# Badge_03v2-prog-schem.net
KiCad netlist of a schematic drawn in EAGLE
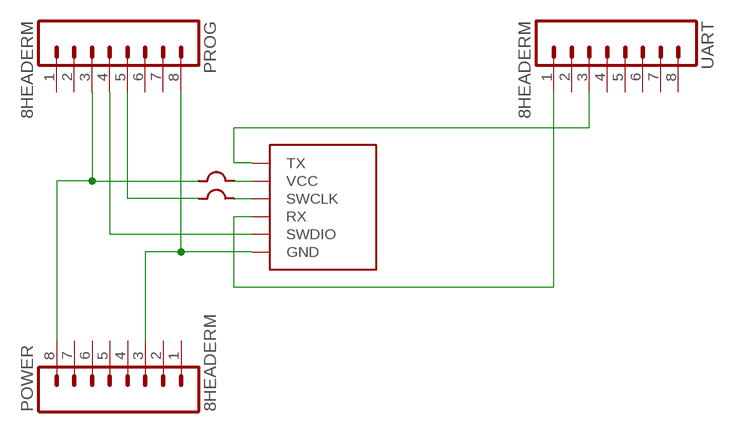
[diagram p0: schematic, sheet 1]

(export (version "E")
  (design (tool "Eeschema 10.0.6"))
  (components
    (comp (ref "J1")
      (value "PROG_CONN_6")
      (footprint "eagle-import:TH_CONN_6")
      (libsource (lib "eagle-import") (part "PROG_CONN_6"))
    )
    (comp (ref "POWER")
      (value "8HEADERM")
      (footprint "eagle-import:1X08_ROUND")
      (libsource (lib "eagle-import") (part "8HEADERM"))
    )
    (comp (ref "PROG")
      (value "8HEADERM")
      (footprint "eagle-import:1X08_ROUND")
      (libsource (lib "eagle-import") (part "8HEADERM"))
    )
    (comp (ref "U$1")
      (value "JUMPER")
      (footprint "eagle-import:1206")
      (libsource (lib "eagle-import") (part "JUMPER"))
    )
    (comp (ref "U$2")
      (value "JUMPER")
      (footprint "eagle-import:1206")
      (libsource (lib "eagle-import") (part "JUMPER"))
    )
    (comp (ref "UART")
      (value "8HEADERM")
      (footprint "eagle-import:1X08_ROUND")
      (libsource (lib "eagle-import") (part "8HEADERM"))
    )
  )
  (nets
    (net (code "1") (name "Net-(J1-PadGND)") (class "Default")
      (node (ref "J1") (pin "GND") (pinfunction "GND_GND") (pintype "bidirectional"))
      (node (ref "POWER") (pin "3") (pinfunction "3_3") (pintype "passive"))
      (node (ref "PROG") (pin "8") (pinfunction "8_8") (pintype "passive"))
    )
    (net (code "2") (name "Net-(J1-PadRX)") (class "Default")
      (node (ref "J1") (pin "RX") (pinfunction "RX_RX") (pintype "bidirectional"))
      (node (ref "UART") (pin "1") (pinfunction "1_1") (pintype "passive"))
    )
    (net (code "3") (name "Net-(J1-PadSWDIO)") (class "Default")
      (node (ref "J1") (pin "SWDIO") (pinfunction "SWDIO_SWDIO") (pintype "bidirectional"))
      (node (ref "PROG") (pin "4") (pinfunction "4_4") (pintype "passive"))
    )
    (net (code "4") (name "Net-(J1-PadTX)") (class "Default")
      (node (ref "J1") (pin "TX") (pinfunction "TX_TX") (pintype "bidirectional"))
      (node (ref "UART") (pin "3") (pinfunction "3_3") (pintype "passive"))
    )
    (net (code "5") (name "Net-(U$1-P$1)") (class "Default")
      (node (ref "POWER") (pin "8") (pinfunction "8_8") (pintype "passive"))
      (node (ref "PROG") (pin "3") (pinfunction "3_3") (pintype "passive"))
      (node (ref "U$1") (pin "1") (pinfunction "P$1_1") (pintype "bidirectional"))
    )
    (net (code "6") (name "Net-(U$1-P$2)") (class "Default")
      (node (ref "J1") (pin "VCC") (pinfunction "VCC_VCC") (pintype "bidirectional"))
      (node (ref "U$1") (pin "2") (pinfunction "P$2_2") (pintype "bidirectional"))
    )
    (net (code "7") (name "Net-(U$2-P$1)") (class "Default")
      (node (ref "PROG") (pin "5") (pinfunction "5_5") (pintype "passive"))
      (node (ref "U$2") (pin "1") (pinfunction "P$1_1") (pintype "bidirectional"))
    )
    (net (code "8") (name "Net-(U$2-P$2)") (class "Default")
      (node (ref "J1") (pin "SWCLK") (pinfunction "SWCLK_SWCLK") (pintype "bidirectional"))
      (node (ref "U$2") (pin "2") (pinfunction "P$2_2") (pintype "bidirectional"))
    )
    (net (code "9") (name "unconnected-(POWER-Pad1)") (class "Default")
      (node (ref "POWER") (pin "1") (pinfunction "1_1") (pintype "passive"))
    )
    (net (code "10") (name "unconnected-(POWER-Pad2)") (class "Default")
      (node (ref "POWER") (pin "2") (pinfunction "2_2") (pintype "passive"))
    )
    (net (code "11") (name "unconnected-(POWER-Pad4)") (class "Default")
      (node (ref "POWER") (pin "4") (pinfunction "4_4") (pintype "passive"))
    )
    (net (code "12") (name "unconnected-(POWER-Pad5)") (class "Default")
      (node (ref "POWER") (pin "5") (pinfunction "5_5") (pintype "passive"))
    )
    (net (code "13") (name "unconnected-(POWER-Pad6)") (class "Default")
      (node (ref "POWER") (pin "6") (pinfunction "6_6") (pintype "passive"))
    )
    (net (code "14") (name "unconnected-(POWER-Pad7)") (class "Default")
      (node (ref "POWER") (pin "7") (pinfunction "7_7") (pintype "passive"))
    )
    (net (code "15") (name "unconnected-(PROG-Pad1)") (class "Default")
      (node (ref "PROG") (pin "1") (pinfunction "1_1") (pintype "passive"))
    )
    (net (code "16") (name "unconnected-(PROG-Pad2)") (class "Default")
      (node (ref "PROG") (pin "2") (pinfunction "2_2") (pintype "passive"))
    )
    (net (code "17") (name "unconnected-(PROG-Pad6)") (class "Default")
      (node (ref "PROG") (pin "6") (pinfunction "6_6") (pintype "passive"))
    )
    (net (code "18") (name "unconnected-(PROG-Pad7)") (class "Default")
      (node (ref "PROG") (pin "7") (pinfunction "7_7") (pintype "passive"))
    )
    (net (code "19") (name "unconnected-(UART-Pad2)") (class "Default")
      (node (ref "UART") (pin "2") (pinfunction "2_2") (pintype "passive"))
    )
    (net (code "20") (name "unconnected-(UART-Pad4)") (class "Default")
      (node (ref "UART") (pin "4") (pinfunction "4_4") (pintype "passive"))
    )
    (net (code "21") (name "unconnected-(UART-Pad5)") (class "Default")
      (node (ref "UART") (pin "5") (pinfunction "5_5") (pintype "passive"))
    )
    (net (code "22") (name "unconnected-(UART-Pad6)") (class "Default")
      (node (ref "UART") (pin "6") (pinfunction "6_6") (pintype "passive"))
    )
    (net (code "23") (name "unconnected-(UART-Pad7)") (class "Default")
      (node (ref "UART") (pin "7") (pinfunction "7_7") (pintype "passive"))
    )
    (net (code "24") (name "unconnected-(UART-Pad8)") (class "Default")
      (node (ref "UART") (pin "8") (pinfunction "8_8") (pintype "passive"))
    )
  )
)
